# IcspAdapter.net
KiCad netlist of a schematic drawn in EAGLE
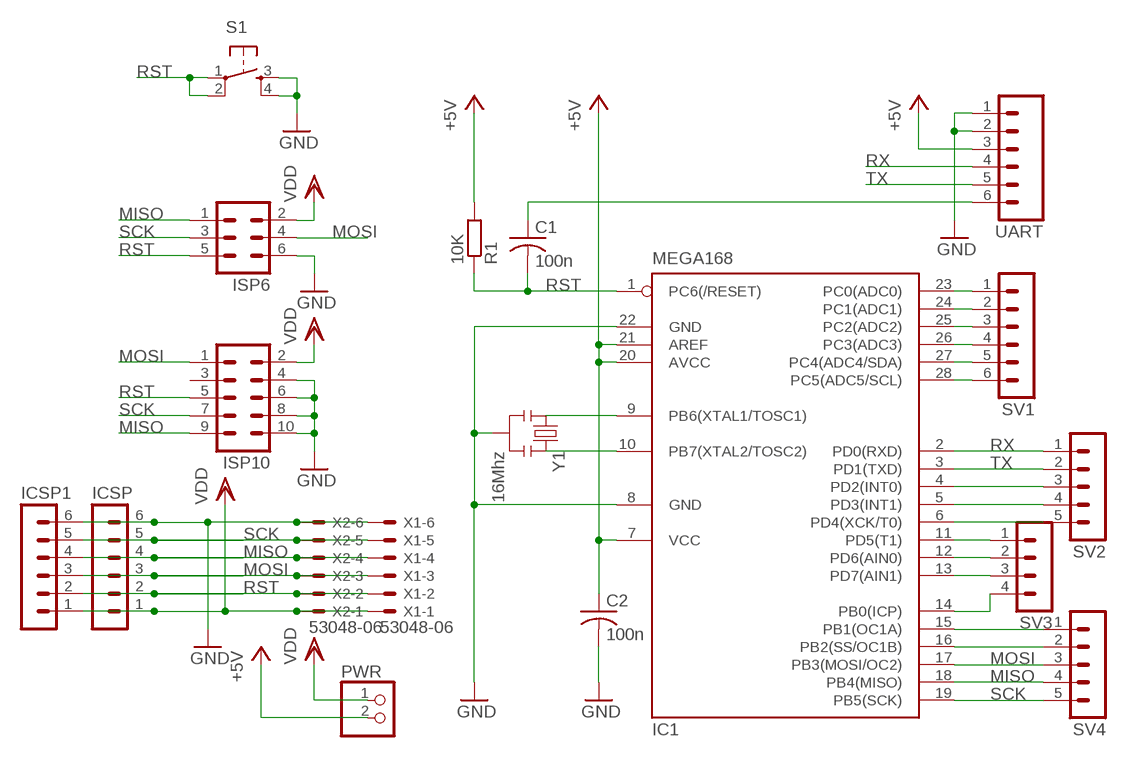
[diagram p0: schematic, sheet 1]

(export (version "E")
  (design (tool "Eeschema 10.0.6"))
  (components
    (comp (ref "C1")
      (value "100n")
      (footprint "eagle-import:C050-024X044")
      (libsource (lib "eagle-import") (part "C-US050-024X044"))
    )
    (comp (ref "C2")
      (value "100n")
      (footprint "eagle-import:C050-024X044")
      (libsource (lib "eagle-import") (part "C-US050-024X044"))
    )
    (comp (ref "IC1")
      (value "MEGA168")
      (footprint "eagle-import:DIL28-3")
      (libsource (lib "eagle-import") (part "MEGA8-P"))
    )
    (comp (ref "ICSP")
      (value "MA06-1")
      (footprint "eagle-import:MA06-1")
      (libsource (lib "eagle-import") (part "MA06-1"))
    )
    (comp (ref "ICSP1")
      (value "MA06-1")
      (footprint "eagle-import:MA06-1")
      (libsource (lib "eagle-import") (part "MA06-1"))
    )
    (comp (ref "ISP6")
      (value "MA03-2")
      (footprint "eagle-import:MA03-2")
      (libsource (lib "eagle-import") (part "MA03-2"))
    )
    (comp (ref "ISP10")
      (value "MA05-2")
      (footprint "eagle-import:MA05-2")
      (libsource (lib "eagle-import") (part "MA05-2"))
    )
    (comp (ref "PWR")
      (value "PINHD-1X2")
      (footprint "eagle-import:1X02")
      (libsource (lib "eagle-import") (part "PINHD-1X2"))
    )
    (comp (ref "R1")
      (value "10K")
      (footprint "eagle-import:0204_7")
      (libsource (lib "eagle-import") (part "R-EU_0204/7"))
    )
    (comp (ref "S1")
      (value "TAC_SWITCHPTH")
      (footprint "eagle-import:TACTILE-PTH")
      (libsource (lib "eagle-import") (part "TAC_SWITCHPTH"))
    )
    (comp (ref "SV1")
      (value "MA06-1")
      (footprint "eagle-import:MA06-1")
      (libsource (lib "eagle-import") (part "MA06-1"))
    )
    (comp (ref "SV2")
      (value "MA05-1")
      (footprint "eagle-import:MA05-1")
      (libsource (lib "eagle-import") (part "MA05-1"))
    )
    (comp (ref "SV3")
      (value "MA04-1")
      (footprint "eagle-import:MA04-1")
      (libsource (lib "eagle-import") (part "MA04-1"))
    )
    (comp (ref "SV4")
      (value "MA05-1")
      (footprint "eagle-import:MA05-1")
      (libsource (lib "eagle-import") (part "MA05-1"))
    )
    (comp (ref "UART")
      (value "M06SIP")
      (footprint "eagle-import:1X06")
      (libsource (lib "eagle-import") (part "M06SIP"))
    )
    (comp (ref "X1")
      (value "53048-06")
      (footprint "eagle-import:53048-06")
      (fields (field (name "MF") "WALDOM/MOLEX") (field (name "MPN") "53048-0610"))
      (libsource (lib "eagle-import") (part "53?-06048"))
    )
    (comp (ref "X2")
      (value "53048-06")
      (footprint "eagle-import:53048-06")
      (fields (field (name "MF") "WALDOM/MOLEX") (field (name "MPN") "53048-0610"))
      (libsource (lib "eagle-import") (part "53?-06048"))
    )
    (comp (ref "Y1")
      (value "16Mhz")
      (footprint "eagle-import:RESONATOR-PTH")
      (libsource (lib "eagle-import") (part "RESONATORPTH"))
    )
  )
  (nets
    (net (code "1") (name "+5V") (class "Default")
      (node (ref "C2") (pin "1") (pinfunction "1_1") (pintype "passive"))
      (node (ref "IC1") (pin "20") (pinfunction "AVCC_20") (pintype "power_in"))
      (node (ref "IC1") (pin "21") (pinfunction "AREF_21") (pintype "passive"))
      (node (ref "IC1") (pin "7") (pinfunction "VCC_7") (pintype "power_in"))
      (node (ref "PWR") (pin "2") (pinfunction "2_2") (pintype "passive"))
      (node (ref "R1") (pin "2") (pinfunction "2_2") (pintype "passive"))
      (node (ref "UART") (pin "3") (pinfunction "3_3") (pintype "passive"))
    )
    (net (code "2") (name "/MISO") (class "Default")
      (node (ref "IC1") (pin "18") (pinfunction "PB4(MISO)_18") (pintype "bidirectional"))
      (node (ref "ICSP") (pin "4") (pinfunction "4_4") (pintype "passive"))
      (node (ref "ICSP1") (pin "4") (pinfunction "4_4") (pintype "passive"))
      (node (ref "ISP10") (pin "9") (pinfunction "9_9") (pintype "passive"))
      (node (ref "ISP6") (pin "1") (pinfunction "1_1") (pintype "passive"))
      (node (ref "SV4") (pin "4") (pinfunction "4_4") (pintype "passive"))
      (node (ref "X1") (pin "4") (pinfunction "S_4") (pintype "passive"))
      (node (ref "X2") (pin "4") (pinfunction "S_4") (pintype "passive"))
    )
    (net (code "3") (name "/MOSI") (class "Default")
      (node (ref "IC1") (pin "17") (pinfunction "PB3(MOSI/OC2)_17") (pintype "bidirectional"))
      (node (ref "ICSP") (pin "3") (pinfunction "3_3") (pintype "passive"))
      (node (ref "ICSP1") (pin "3") (pinfunction "3_3") (pintype "passive"))
      (node (ref "ISP10") (pin "1") (pinfunction "1_1") (pintype "passive"))
      (node (ref "ISP6") (pin "4") (pinfunction "4_4") (pintype "passive"))
      (node (ref "SV4") (pin "3") (pinfunction "3_3") (pintype "passive"))
      (node (ref "X1") (pin "3") (pinfunction "S_3") (pintype "passive"))
      (node (ref "X2") (pin "3") (pinfunction "S_3") (pintype "passive"))
    )
    (net (code "4") (name "/RST") (class "Default")
      (node (ref "C1") (pin "2") (pinfunction "2_2") (pintype "passive"))
      (node (ref "IC1") (pin "1") (pinfunction "PC6(/RESET)_1") (pintype "bidirectional"))
      (node (ref "ICSP") (pin "2") (pinfunction "2_2") (pintype "passive"))
      (node (ref "ICSP1") (pin "2") (pinfunction "2_2") (pintype "passive"))
      (node (ref "ISP10") (pin "5") (pinfunction "5_5") (pintype "passive"))
      (node (ref "ISP6") (pin "5") (pinfunction "5_5") (pintype "passive"))
      (node (ref "R1") (pin "1") (pinfunction "1_1") (pintype "passive"))
      (node (ref "S1") (pin "1") (pinfunction "1_1") (pintype "passive"))
      (node (ref "S1") (pin "2") (pinfunction "2_2") (pintype "passive"))
      (node (ref "X1") (pin "2") (pinfunction "S_2") (pintype "passive"))
      (node (ref "X2") (pin "2") (pinfunction "S_2") (pintype "passive"))
    )
    (net (code "5") (name "/RX") (class "Default")
      (node (ref "IC1") (pin "2") (pinfunction "PD0(RXD)_2") (pintype "bidirectional"))
      (node (ref "SV2") (pin "1") (pinfunction "1_1") (pintype "passive"))
      (node (ref "UART") (pin "4") (pinfunction "4_4") (pintype "passive"))
    )
    (net (code "6") (name "/SCK") (class "Default")
      (node (ref "IC1") (pin "19") (pinfunction "PB5(SCK)_19") (pintype "bidirectional"))
      (node (ref "ICSP") (pin "5") (pinfunction "5_5") (pintype "passive"))
      (node (ref "ICSP1") (pin "5") (pinfunction "5_5") (pintype "passive"))
      (node (ref "ISP10") (pin "7") (pinfunction "7_7") (pintype "passive"))
      (node (ref "ISP6") (pin "3") (pinfunction "3_3") (pintype "passive"))
      (node (ref "SV4") (pin "5") (pinfunction "5_5") (pintype "passive"))
      (node (ref "X1") (pin "5") (pinfunction "S_5") (pintype "passive"))
      (node (ref "X2") (pin "5") (pinfunction "S_5") (pintype "passive"))
    )
    (net (code "7") (name "/TX") (class "Default")
      (node (ref "IC1") (pin "3") (pinfunction "PD1(TXD)_3") (pintype "bidirectional"))
      (node (ref "SV2") (pin "2") (pinfunction "2_2") (pintype "passive"))
      (node (ref "UART") (pin "5") (pinfunction "5_5") (pintype "passive"))
    )
    (net (code "8") (name "GND") (class "Default")
      (node (ref "C2") (pin "2") (pinfunction "2_2") (pintype "passive"))
      (node (ref "IC1") (pin "22") (pinfunction "GND_22") (pintype "power_in"))
      (node (ref "IC1") (pin "8") (pinfunction "GND_8") (pintype "power_in"))
      (node (ref "ICSP") (pin "6") (pinfunction "6_6") (pintype "passive"))
      (node (ref "ICSP1") (pin "6") (pinfunction "6_6") (pintype "passive"))
      (node (ref "ISP10") (pin "10") (pinfunction "10_10") (pintype "passive"))
      (node (ref "ISP10") (pin "4") (pinfunction "4_4") (pintype "passive"))
      (node (ref "ISP10") (pin "6") (pinfunction "6_6") (pintype "passive"))
      (node (ref "ISP10") (pin "8") (pinfunction "8_8") (pintype "passive"))
      (node (ref "ISP6") (pin "6") (pinfunction "6_6") (pintype "passive"))
      (node (ref "S1") (pin "3") (pinfunction "3_3") (pintype "passive"))
      (node (ref "S1") (pin "4") (pinfunction "4_4") (pintype "passive"))
      (node (ref "UART") (pin "1") (pinfunction "1_1") (pintype "passive"))
      (node (ref "UART") (pin "2") (pinfunction "2_2") (pintype "passive"))
      (node (ref "X1") (pin "6") (pinfunction "S_6") (pintype "passive"))
      (node (ref "X2") (pin "6") (pinfunction "S_6") (pintype "passive"))
      (node (ref "Y1") (pin "2") (pinfunction "2_2") (pintype "passive"))
    )
    (net (code "9") (name "Net-(C1-Pad1)") (class "Default")
      (node (ref "C1") (pin "1") (pinfunction "1_1") (pintype "passive"))
      (node (ref "UART") (pin "6") (pinfunction "6_6") (pintype "passive"))
    )
    (net (code "10") (name "Net-(IC1-PB0(ICP))") (class "Default")
      (node (ref "IC1") (pin "14") (pinfunction "PB0(ICP)_14") (pintype "bidirectional"))
      (node (ref "SV3") (pin "4") (pinfunction "4_4") (pintype "passive"))
    )
    (net (code "11") (name "Net-(IC1-PB1(OC1A))") (class "Default")
      (node (ref "IC1") (pin "15") (pinfunction "PB1(OC1A)_15") (pintype "bidirectional"))
      (node (ref "SV4") (pin "1") (pinfunction "1_1") (pintype "passive"))
    )
    (net (code "12") (name "Net-(IC1-PB2(SS{slash}OC1B))") (class "Default")
      (node (ref "IC1") (pin "16") (pinfunction "PB2(SS/OC1B)_16") (pintype "bidirectional"))
      (node (ref "SV4") (pin "2") (pinfunction "2_2") (pintype "passive"))
    )
    (net (code "13") (name "Net-(IC1-PB6(XTAL1{slash}TOSC1))") (class "Default")
      (node (ref "IC1") (pin "9") (pinfunction "PB6(XTAL1/TOSC1)_9") (pintype "bidirectional"))
      (node (ref "Y1") (pin "1") (pinfunction "1_1") (pintype "passive"))
    )
    (net (code "14") (name "Net-(IC1-PB7(XTAL2{slash}TOSC2))") (class "Default")
      (node (ref "IC1") (pin "10") (pinfunction "PB7(XTAL2/TOSC2)_10") (pintype "bidirectional"))
      (node (ref "Y1") (pin "3") (pinfunction "3_3") (pintype "passive"))
    )
    (net (code "15") (name "Net-(IC1-PC0(ADC0))") (class "Default")
      (node (ref "IC1") (pin "23") (pinfunction "PC0(ADC0)_23") (pintype "bidirectional"))
      (node (ref "SV1") (pin "1") (pinfunction "1_1") (pintype "passive"))
    )
    (net (code "16") (name "Net-(IC1-PC1(ADC1))") (class "Default")
      (node (ref "IC1") (pin "24") (pinfunction "PC1(ADC1)_24") (pintype "bidirectional"))
      (node (ref "SV1") (pin "2") (pinfunction "2_2") (pintype "passive"))
    )
    (net (code "17") (name "Net-(IC1-PC2(ADC2))") (class "Default")
      (node (ref "IC1") (pin "25") (pinfunction "PC2(ADC2)_25") (pintype "bidirectional"))
      (node (ref "SV1") (pin "3") (pinfunction "3_3") (pintype "passive"))
    )
    (net (code "18") (name "Net-(IC1-PC3(ADC3))") (class "Default")
      (node (ref "IC1") (pin "26") (pinfunction "PC3(ADC3)_26") (pintype "bidirectional"))
      (node (ref "SV1") (pin "4") (pinfunction "4_4") (pintype "passive"))
    )
    (net (code "19") (name "Net-(IC1-PC4(ADC4{slash}SDA))") (class "Default")
      (node (ref "IC1") (pin "27") (pinfunction "PC4(ADC4/SDA)_27") (pintype "bidirectional"))
      (node (ref "SV1") (pin "5") (pinfunction "5_5") (pintype "passive"))
    )
    (net (code "20") (name "Net-(IC1-PC5(ADC5{slash}SCL))") (class "Default")
      (node (ref "IC1") (pin "28") (pinfunction "PC5(ADC5/SCL)_28") (pintype "bidirectional"))
      (node (ref "SV1") (pin "6") (pinfunction "6_6") (pintype "passive"))
    )
    (net (code "21") (name "Net-(IC1-PD2(INT0))") (class "Default")
      (node (ref "IC1") (pin "4") (pinfunction "PD2(INT0)_4") (pintype "bidirectional"))
      (node (ref "SV2") (pin "3") (pinfunction "3_3") (pintype "passive"))
    )
    (net (code "22") (name "Net-(IC1-PD3(INT1))") (class "Default")
      (node (ref "IC1") (pin "5") (pinfunction "PD3(INT1)_5") (pintype "bidirectional"))
      (node (ref "SV2") (pin "4") (pinfunction "4_4") (pintype "passive"))
    )
    (net (code "23") (name "Net-(IC1-PD4(XCK{slash}T0))") (class "Default")
      (node (ref "IC1") (pin "6") (pinfunction "PD4(XCK/T0)_6") (pintype "bidirectional"))
      (node (ref "SV2") (pin "5") (pinfunction "5_5") (pintype "passive"))
    )
    (net (code "24") (name "Net-(IC1-PD5(T1))") (class "Default")
      (node (ref "IC1") (pin "11") (pinfunction "PD5(T1)_11") (pintype "bidirectional"))
      (node (ref "SV3") (pin "1") (pinfunction "1_1") (pintype "passive"))
    )
    (net (code "25") (name "Net-(IC1-PD6(AIN0))") (class "Default")
      (node (ref "IC1") (pin "12") (pinfunction "PD6(AIN0)_12") (pintype "bidirectional"))
      (node (ref "SV3") (pin "2") (pinfunction "2_2") (pintype "passive"))
    )
    (net (code "26") (name "Net-(IC1-PD7(AIN1))") (class "Default")
      (node (ref "IC1") (pin "13") (pinfunction "PD7(AIN1)_13") (pintype "bidirectional"))
      (node (ref "SV3") (pin "3") (pinfunction "3_3") (pintype "passive"))
    )
    (net (code "27") (name "VDD") (class "Default")
      (node (ref "ICSP") (pin "1") (pinfunction "1_1") (pintype "passive"))
      (node (ref "ICSP1") (pin "1") (pinfunction "1_1") (pintype "passive"))
      (node (ref "ISP10") (pin "2") (pinfunction "2_2") (pintype "passive"))
      (node (ref "ISP6") (pin "2") (pinfunction "2_2") (pintype "passive"))
      (node (ref "PWR") (pin "1") (pinfunction "1_1") (pintype "passive"))
      (node (ref "X1") (pin "1") (pinfunction "S_1") (pintype "passive"))
      (node (ref "X2") (pin "1") (pinfunction "S_1") (pintype "passive"))
    )
    (net (code "28") (name "unconnected-(ISP10-Pad3)") (class "Default")
      (node (ref "ISP10") (pin "3") (pinfunction "3_3") (pintype "passive"))
    )
  )
)
